# axios_sensor_rev1.net
KiCad netlist of a schematic drawn in EAGLE
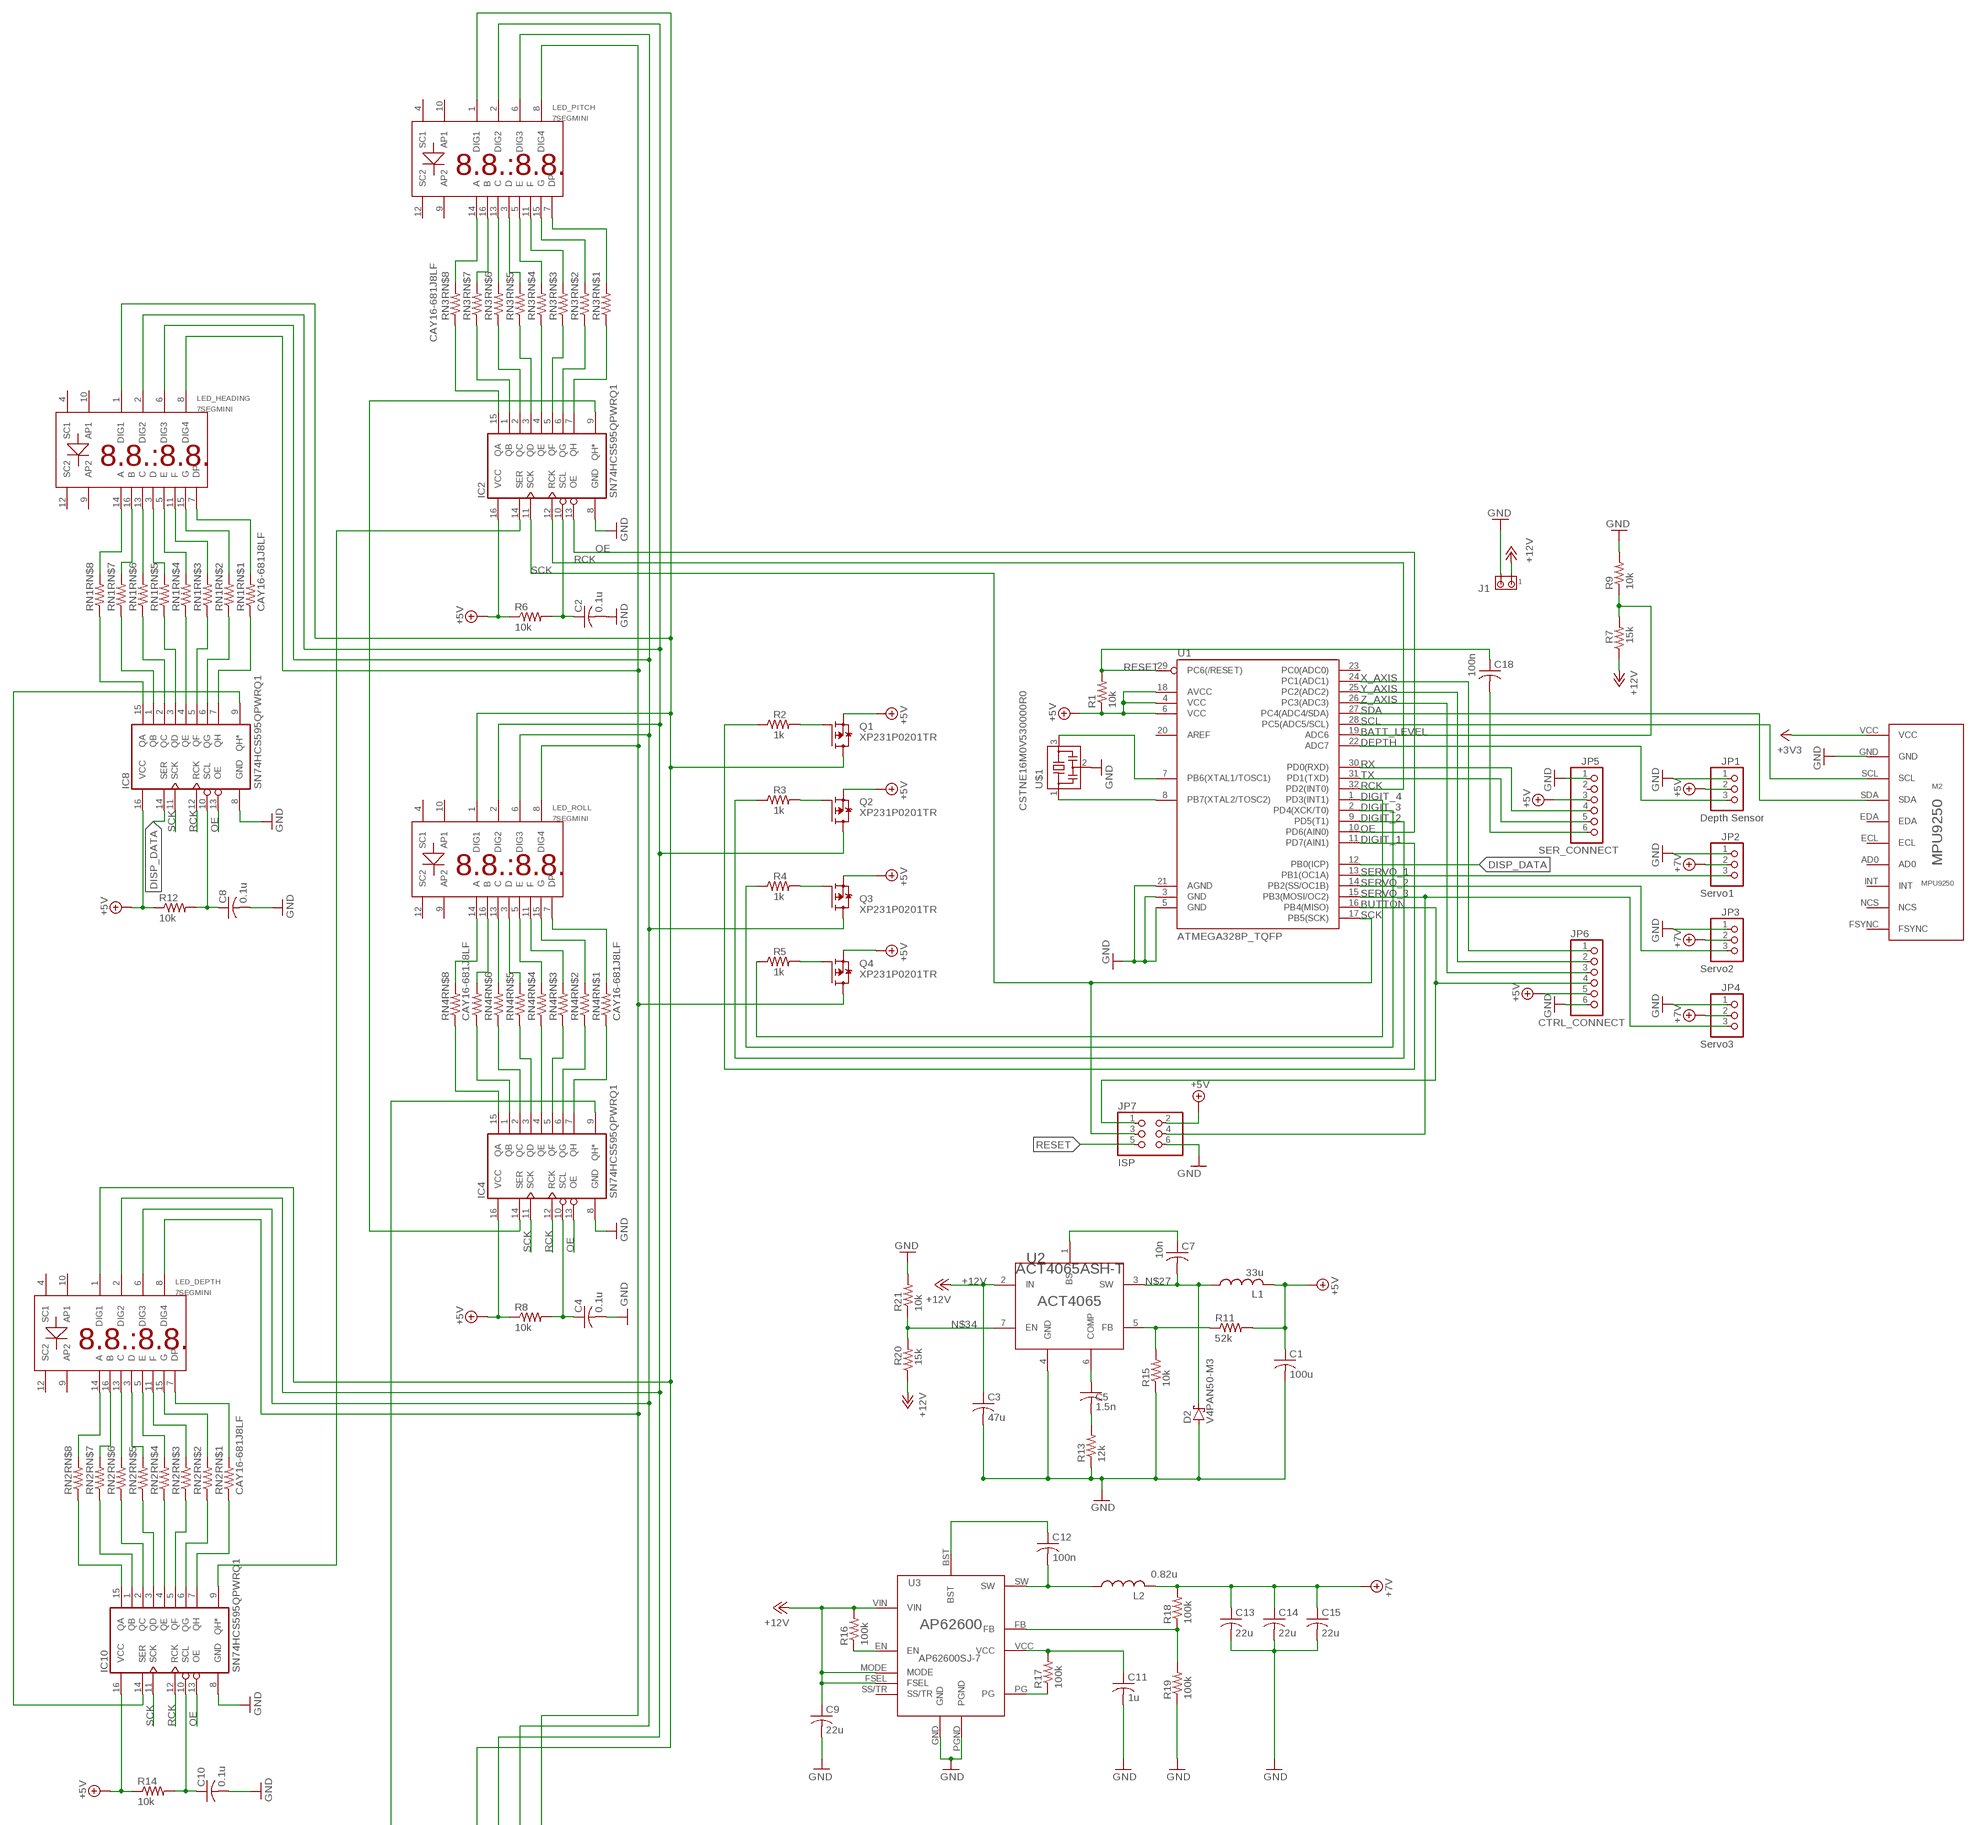
[diagram p0: schematic, sheet 1, part 1 of 2]
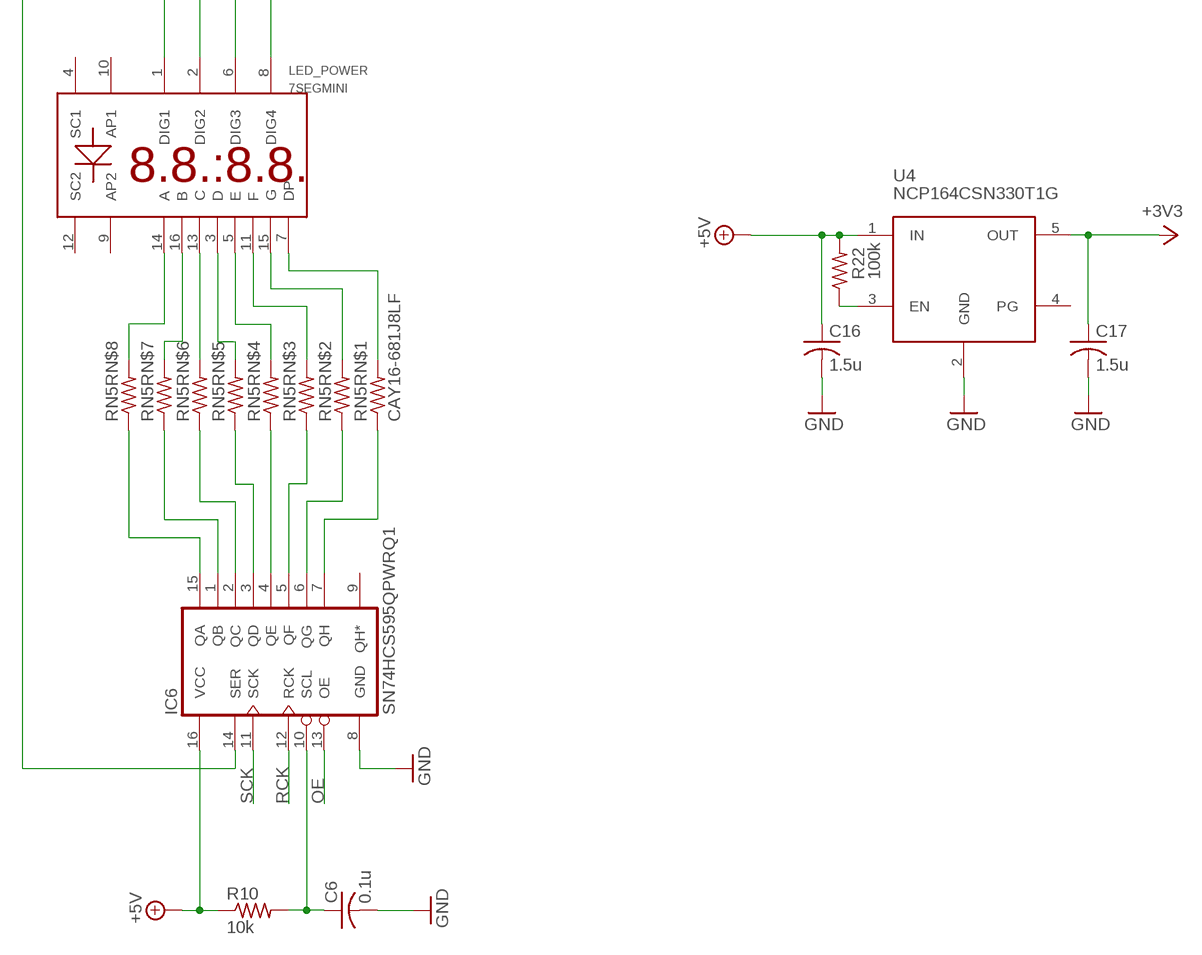
[diagram p1: schematic, sheet 1, part 2 of 2]

(export (version "E")
  (design (tool "Eeschema 10.0.6"))
  (components
    (comp (ref "C1")
      (value "100u")
      (footprint "eagle-import:C0603")
      (libsource (lib "eagle-import") (part "C-USC0603"))
    )
    (comp (ref "C2")
      (value "0.1u")
      (footprint "eagle-import:C0603")
      (libsource (lib "eagle-import") (part "C-USC0603"))
    )
    (comp (ref "C3")
      (value "47u")
      (footprint "eagle-import:C0603")
      (libsource (lib "eagle-import") (part "C-USC0603"))
    )
    (comp (ref "C4")
      (value "0.1u")
      (footprint "eagle-import:C0603")
      (libsource (lib "eagle-import") (part "C-USC0603"))
    )
    (comp (ref "C5")
      (value "1.5n")
      (footprint "eagle-import:C0603")
      (libsource (lib "eagle-import") (part "C-USC0603"))
    )
    (comp (ref "C6")
      (value "0.1u")
      (footprint "eagle-import:C0603")
      (libsource (lib "eagle-import") (part "C-USC0603"))
    )
    (comp (ref "C7")
      (value "10n")
      (footprint "eagle-import:C0603")
      (libsource (lib "eagle-import") (part "C-USC0603"))
    )
    (comp (ref "C8")
      (value "0.1u")
      (footprint "eagle-import:C0603")
      (libsource (lib "eagle-import") (part "C-USC0603"))
    )
    (comp (ref "C9")
      (value "22u")
      (footprint "eagle-import:C0603")
      (libsource (lib "eagle-import") (part "C-USC0603"))
    )
    (comp (ref "C10")
      (value "0.1u")
      (footprint "eagle-import:C0603")
      (libsource (lib "eagle-import") (part "C-USC0603"))
    )
    (comp (ref "C11")
      (value "1u")
      (footprint "eagle-import:C0603")
      (libsource (lib "eagle-import") (part "C-USC0603"))
    )
    (comp (ref "C12")
      (value "100n")
      (footprint "eagle-import:C0603")
      (libsource (lib "eagle-import") (part "C-USC0603"))
    )
    (comp (ref "C13")
      (value "22u")
      (footprint "eagle-import:C0603")
      (libsource (lib "eagle-import") (part "C-USC0603"))
    )
    (comp (ref "C14")
      (value "22u")
      (footprint "eagle-import:C0603")
      (libsource (lib "eagle-import") (part "C-USC0603"))
    )
    (comp (ref "C15")
      (value "22u")
      (footprint "eagle-import:C0603")
      (libsource (lib "eagle-import") (part "C-USC0603"))
    )
    (comp (ref "C16")
      (value "1.5u")
      (footprint "eagle-import:C0603")
      (libsource (lib "eagle-import") (part "C-USC0603"))
    )
    (comp (ref "C17")
      (value "1.5u")
      (footprint "eagle-import:C0603")
      (libsource (lib "eagle-import") (part "C-USC0603"))
    )
    (comp (ref "C18")
      (value "100n")
      (footprint "eagle-import:C0603")
      (libsource (lib "eagle-import") (part "C-USC0603"))
    )
    (comp (ref "D2")
      (value "V4PAN50-M3")
      (footprint "eagle-import:SMPA")
      (libsource (lib "eagle-import") (part "V4PAN50-M3"))
    )
    (comp (ref "IC2")
      (value "SN74HCS595QPWRQ1")
      (footprint "eagle-import:TSSOP16")
      (libsource (lib "eagle-import") (part "SN74HCS595QPWRQ1"))
    )
    (comp (ref "IC4")
      (value "SN74HCS595QPWRQ1")
      (footprint "eagle-import:TSSOP16")
      (libsource (lib "eagle-import") (part "SN74HCS595QPWRQ1"))
    )
    (comp (ref "IC6")
      (value "SN74HCS595QPWRQ1")
      (footprint "eagle-import:TSSOP16")
      (libsource (lib "eagle-import") (part "SN74HCS595QPWRQ1"))
    )
    (comp (ref "IC8")
      (value "SN74HCS595QPWRQ1")
      (footprint "eagle-import:TSSOP16")
      (libsource (lib "eagle-import") (part "SN74HCS595QPWRQ1"))
    )
    (comp (ref "IC10")
      (value "SN74HCS595QPWRQ1")
      (footprint "eagle-import:TSSOP16")
      (libsource (lib "eagle-import") (part "SN74HCS595QPWRQ1"))
    )
    (comp (ref "J1")
      (value "MTA02-156")
      (footprint "eagle-import:1X2MTA")
      (libsource (lib "eagle-import") (part "MTA02-156"))
    )
    (comp (ref "JP1")
      (value "Depth Sensor")
      (footprint "eagle-import:1X03")
      (libsource (lib "eagle-import") (part "PINHD-1X3"))
    )
    (comp (ref "JP2")
      (value "Servo1")
      (footprint "eagle-import:1X03")
      (libsource (lib "eagle-import") (part "PINHD-1X3"))
    )
    (comp (ref "JP3")
      (value "Servo2")
      (footprint "eagle-import:1X03")
      (libsource (lib "eagle-import") (part "PINHD-1X3"))
    )
    (comp (ref "JP4")
      (value "Servo3")
      (footprint "eagle-import:1X03")
      (libsource (lib "eagle-import") (part "PINHD-1X3"))
    )
    (comp (ref "JP5")
      (value "SER_CONNECT")
      (footprint "eagle-import:1X06")
      (libsource (lib "eagle-import") (part "PINHD-1X6"))
    )
    (comp (ref "JP6")
      (value "CTRL_CONNECT")
      (footprint "eagle-import:1X06")
      (libsource (lib "eagle-import") (part "PINHD-1X6"))
    )
    (comp (ref "JP7")
      (value "ISP")
      (footprint "eagle-import:2X03")
      (libsource (lib "eagle-import") (part "PINHD-2X3"))
    )
    (comp (ref "L1")
      (value "33u")
      (footprint "eagle-import:SRN1060-330M")
      (libsource (lib "eagle-import") (part "SRN1060-330M"))
    )
    (comp (ref "L2")
      (value "0.82u")
      (footprint "eagle-import:ECS-MPIL0630-R82MC")
      (libsource (lib "eagle-import") (part "ECS-MPIL0630-R82MC"))
    )
    (comp (ref "LED_DEPTH")
      (value "7SEGMINI")
      (footprint "eagle-import:7SEGMINI")
      (libsource (lib "eagle-import") (part "7SEGMINI"))
    )
    (comp (ref "LED_HEADING")
      (value "7SEGMINI")
      (footprint "eagle-import:7SEGMINI")
      (libsource (lib "eagle-import") (part "7SEGMINI"))
    )
    (comp (ref "LED_PITCH")
      (value "7SEGMINI")
      (footprint "eagle-import:7SEGMINI")
      (libsource (lib "eagle-import") (part "7SEGMINI"))
    )
    (comp (ref "LED_POWER")
      (value "7SEGMINI")
      (footprint "eagle-import:7SEGMINI")
      (libsource (lib "eagle-import") (part "7SEGMINI"))
    )
    (comp (ref "LED_ROLL")
      (value "7SEGMINI")
      (footprint "eagle-import:7SEGMINI")
      (libsource (lib "eagle-import") (part "7SEGMINI"))
    )
    (comp (ref "M2")
      (value "MPU9250")
      (footprint "eagle-import:MPU9250")
      (libsource (lib "eagle-import") (part "MPU9250"))
    )
    (comp (ref "Q1")
      (value "XP231P0201TR")
      (footprint "eagle-import:SOT23")
      (libsource (lib "eagle-import") (part "XP231P0201TR"))
    )
    (comp (ref "Q2")
      (value "XP231P0201TR")
      (footprint "eagle-import:SOT23")
      (libsource (lib "eagle-import") (part "XP231P0201TR"))
    )
    (comp (ref "Q3")
      (value "XP231P0201TR")
      (footprint "eagle-import:SOT23")
      (libsource (lib "eagle-import") (part "XP231P0201TR"))
    )
    (comp (ref "Q4")
      (value "XP231P0201TR")
      (footprint "eagle-import:SOT23")
      (libsource (lib "eagle-import") (part "XP231P0201TR"))
    )
    (comp (ref "R1")
      (value "10k")
      (footprint "eagle-import:R0603")
      (libsource (lib "eagle-import") (part "R-US_R0603"))
    )
    (comp (ref "R2")
      (value "1k")
      (footprint "eagle-import:R0603")
      (libsource (lib "eagle-import") (part "R-US_R0603"))
    )
    (comp (ref "R3")
      (value "1k")
      (footprint "eagle-import:R0603")
      (libsource (lib "eagle-import") (part "R-US_R0603"))
    )
    (comp (ref "R4")
      (value "1k")
      (footprint "eagle-import:R0603")
      (libsource (lib "eagle-import") (part "R-US_R0603"))
    )
    (comp (ref "R5")
      (value "1k")
      (footprint "eagle-import:R0603")
      (libsource (lib "eagle-import") (part "R-US_R0603"))
    )
    (comp (ref "R6")
      (value "10k")
      (footprint "eagle-import:R0603")
      (libsource (lib "eagle-import") (part "R-US_R0603"))
    )
    (comp (ref "R7")
      (value "15k")
      (footprint "eagle-import:R0603")
      (libsource (lib "eagle-import") (part "R-US_R0603"))
    )
    (comp (ref "R8")
      (value "10k")
      (footprint "eagle-import:R0603")
      (libsource (lib "eagle-import") (part "R-US_R0603"))
    )
    (comp (ref "R9")
      (value "10k")
      (footprint "eagle-import:R0603")
      (libsource (lib "eagle-import") (part "R-US_R0603"))
    )
    (comp (ref "R10")
      (value "10k")
      (footprint "eagle-import:R0603")
      (libsource (lib "eagle-import") (part "R-US_R0603"))
    )
    (comp (ref "R11")
      (value "52k")
      (footprint "eagle-import:R0603")
      (libsource (lib "eagle-import") (part "R-US_R0603"))
    )
    (comp (ref "R12")
      (value "10k")
      (footprint "eagle-import:R0603")
      (libsource (lib "eagle-import") (part "R-US_R0603"))
    )
    (comp (ref "R13")
      (value "12k")
      (footprint "eagle-import:R0603")
      (libsource (lib "eagle-import") (part "R-US_R0603"))
    )
    (comp (ref "R14")
      (value "10k")
      (footprint "eagle-import:R0603")
      (libsource (lib "eagle-import") (part "R-US_R0603"))
    )
    (comp (ref "R15")
      (value "10k")
      (footprint "eagle-import:R0603")
      (libsource (lib "eagle-import") (part "R-US_R0603"))
    )
    (comp (ref "R16")
      (value "100k")
      (footprint "eagle-import:R0603")
      (libsource (lib "eagle-import") (part "R-US_R0603"))
    )
    (comp (ref "R17")
      (value "100k")
      (footprint "eagle-import:R0603")
      (libsource (lib "eagle-import") (part "R-US_R0603"))
    )
    (comp (ref "R18")
      (value "100k")
      (footprint "eagle-import:R0603")
      (libsource (lib "eagle-import") (part "R-US_R0603"))
    )
    (comp (ref "R19")
      (value "100k")
      (footprint "eagle-import:R0603")
      (libsource (lib "eagle-import") (part "R-US_R0603"))
    )
    (comp (ref "R20")
      (value "15k")
      (footprint "eagle-import:R0603")
      (libsource (lib "eagle-import") (part "R-US_R0603"))
    )
    (comp (ref "R21")
      (value "10k")
      (footprint "eagle-import:R0603")
      (libsource (lib "eagle-import") (part "R-US_R0603"))
    )
    (comp (ref "R22")
      (value "100k")
      (footprint "eagle-import:R0603")
      (libsource (lib "eagle-import") (part "R-US_R0603"))
    )
    (comp (ref "RN1")
      (value "CAY16-681J8LF")
      (footprint "eagle-import:CAY16-681J8LF")
      (libsource (lib "eagle-import") (part "CAY16-681J8LF"))
    )
    (comp (ref "RN2")
      (value "CAY16-681J8LF")
      (footprint "eagle-import:CAY16-681J8LF")
      (libsource (lib "eagle-import") (part "CAY16-681J8LF"))
    )
    (comp (ref "RN3")
      (value "CAY16-681J8LF")
      (footprint "eagle-import:CAY16-681J8LF")
      (libsource (lib "eagle-import") (part "CAY16-681J8LF"))
    )
    (comp (ref "RN4")
      (value "CAY16-681J8LF")
      (footprint "eagle-import:CAY16-681J8LF")
      (libsource (lib "eagle-import") (part "CAY16-681J8LF"))
    )
    (comp (ref "RN5")
      (value "CAY16-681J8LF")
      (footprint "eagle-import:CAY16-681J8LF")
      (libsource (lib "eagle-import") (part "CAY16-681J8LF"))
    )
    (comp (ref "U$1")
      (value "CSTNE16M0V530000R0")
      (footprint "eagle-import:CSTCR6M")
      (libsource (lib "eagle-import") (part "CSTNE16M0V530000R0"))
    )
    (comp (ref "U1")
      (value "ATMEGA328P_TQFP")
      (footprint "eagle-import:TQFP32-08")
      (libsource (lib "eagle-import") (part "ATMEGA328P_TQFP"))
    )
    (comp (ref "U2")
      (value "ACT4065ASH-T")
      (footprint "eagle-import:SO8")
      (libsource (lib "eagle-import") (part "ACT4065ASH-T"))
    )
    (comp (ref "U3")
      (value "AP62600SJ-7")
      (footprint "eagle-import:V-QFN2030-12")
      (libsource (lib "eagle-import") (part "AP62600SJ-7"))
    )
    (comp (ref "U4")
      (value "NCP164CSN330T1G")
      (footprint "eagle-import:TSOP-5")
      (libsource (lib "eagle-import") (part "NCP164CSN330T1G"))
    )
  )
  (nets
    (net (code "1") (name "+3V3") (class "Default")
      (node (ref "C17") (pin "1") (pinfunction "1_1") (pintype "passive"))
      (node (ref "M2") (pin "VCC") (pinfunction "VCC_VCC") (pintype "bidirectional"))
      (node (ref "U4") (pin "5") (pinfunction "OUT_5") (pintype "bidirectional"))
    )
    (net (code "2") (name "+5V") (class "Default")
      (node (ref "C1") (pin "1") (pinfunction "1_1") (pintype "passive"))
      (node (ref "C16") (pin "1") (pinfunction "1_1") (pintype "passive"))
      (node (ref "IC10") (pin "16") (pinfunction "VCC_16") (pintype "power_in"))
      (node (ref "IC2") (pin "16") (pinfunction "VCC_16") (pintype "power_in"))
      (node (ref "IC4") (pin "16") (pinfunction "VCC_16") (pintype "power_in"))
      (node (ref "IC6") (pin "16") (pinfunction "VCC_16") (pintype "power_in"))
      (node (ref "IC8") (pin "16") (pinfunction "VCC_16") (pintype "power_in"))
      (node (ref "JP1") (pin "2") (pinfunction "2_2") (pintype "passive"))
      (node (ref "JP5") (pin "3") (pinfunction "3_3") (pintype "passive"))
      (node (ref "JP6") (pin "5") (pinfunction "5_5") (pintype "passive"))
      (node (ref "JP7") (pin "2") (pinfunction "2_2") (pintype "passive"))
      (node (ref "L1") (pin "P$2") (pinfunction "2_P$2") (pintype "passive"))
      (node (ref "Q1") (pin "2") (pinfunction "S_2") (pintype "passive"))
      (node (ref "Q2") (pin "2") (pinfunction "S_2") (pintype "passive"))
      (node (ref "Q3") (pin "2") (pinfunction "S_2") (pintype "passive"))
      (node (ref "Q4") (pin "2") (pinfunction "S_2") (pintype "passive"))
      (node (ref "R1") (pin "1") (pinfunction "1_1") (pintype "passive"))
      (node (ref "R10") (pin "1") (pinfunction "1_1") (pintype "passive"))
      (node (ref "R11") (pin "2") (pinfunction "2_2") (pintype "passive"))
      (node (ref "R12") (pin "1") (pinfunction "1_1") (pintype "passive"))
      (node (ref "R14") (pin "1") (pinfunction "1_1") (pintype "passive"))
      (node (ref "R22") (pin "2") (pinfunction "2_2") (pintype "passive"))
      (node (ref "R6") (pin "1") (pinfunction "1_1") (pintype "passive"))
      (node (ref "R8") (pin "1") (pinfunction "1_1") (pintype "passive"))
      (node (ref "U1") (pin "18") (pinfunction "AVCC_18") (pintype "bidirectional"))
      (node (ref "U1") (pin "4") (pinfunction "VCC_4") (pintype "bidirectional"))
      (node (ref "U1") (pin "6") (pinfunction "VCC_6") (pintype "bidirectional"))
      (node (ref "U4") (pin "1") (pinfunction "IN_1") (pintype "bidirectional"))
    )
    (net (code "3") (name "+7V") (class "Default")
      (node (ref "C13") (pin "1") (pinfunction "1_1") (pintype "passive"))
      (node (ref "C14") (pin "1") (pinfunction "1_1") (pintype "passive"))
      (node (ref "C15") (pin "1") (pinfunction "1_1") (pintype "passive"))
      (node (ref "JP2") (pin "2") (pinfunction "2_2") (pintype "passive"))
      (node (ref "JP3") (pin "2") (pinfunction "2_2") (pintype "passive"))
      (node (ref "JP4") (pin "2") (pinfunction "2_2") (pintype "passive"))
      (node (ref "L2") (pin "P$2") (pinfunction "2_P$2") (pintype "passive"))
      (node (ref "R18") (pin "2") (pinfunction "2_2") (pintype "passive"))
    )
    (net (code "4") (name "+12V") (class "Default")
      (node (ref "C3") (pin "1") (pinfunction "1_1") (pintype "passive"))
      (node (ref "C9") (pin "1") (pinfunction "1_1") (pintype "passive"))
      (node (ref "J1") (pin "1") (pinfunction "1_1") (pintype "passive"))
      (node (ref "R16") (pin "2") (pinfunction "2_2") (pintype "passive"))
      (node (ref "R20") (pin "1") (pinfunction "1_1") (pintype "passive"))
      (node (ref "R7") (pin "1") (pinfunction "1_1") (pintype "passive"))
      (node (ref "U2") (pin "2") (pinfunction "IN_2") (pintype "bidirectional"))
      (node (ref "U3") (pin "FSEL") (pinfunction "FSEL_FSEL") (pintype "bidirectional"))
      (node (ref "U3") (pin "MODE") (pinfunction "MODE_MODE") (pintype "bidirectional"))
      (node (ref "U3") (pin "VIN") (pinfunction "VIN_VIN") (pintype "bidirectional"))
    )
    (net (code "5") (name "/BATT_LEVEL") (class "Default")
      (node (ref "R7") (pin "2") (pinfunction "2_2") (pintype "passive"))
      (node (ref "R9") (pin "1") (pinfunction "1_1") (pintype "passive"))
      (node (ref "U1") (pin "19") (pinfunction "ADC6_19") (pintype "bidirectional"))
    )
    (net (code "6") (name "/BUTTON") (class "Default")
      (node (ref "JP6") (pin "4") (pinfunction "4_4") (pintype "passive"))
      (node (ref "JP7") (pin "1") (pinfunction "1_1") (pintype "passive"))
      (node (ref "U1") (pin "16") (pinfunction "PB4(MISO)_16") (pintype "bidirectional"))
    )
    (net (code "7") (name "/DEPTH") (class "Default")
      (node (ref "JP1") (pin "3") (pinfunction "3_3") (pintype "passive"))
      (node (ref "U1") (pin "22") (pinfunction "ADC7_22") (pintype "bidirectional"))
    )
    (net (code "8") (name "/DIGIT_1") (class "Default")
      (node (ref "R2") (pin "1") (pinfunction "1_1") (pintype "passive"))
      (node (ref "U1") (pin "11") (pinfunction "PD7(AIN1)_11") (pintype "bidirectional"))
    )
    (net (code "9") (name "/DIGIT_2") (class "Default")
      (node (ref "R3") (pin "1") (pinfunction "1_1") (pintype "passive"))
      (node (ref "U1") (pin "9") (pinfunction "PD5(T1)_9") (pintype "bidirectional"))
    )
    (net (code "10") (name "/DIGIT_3") (class "Default")
      (node (ref "R4") (pin "1") (pinfunction "1_1") (pintype "passive"))
      (node (ref "U1") (pin "2") (pinfunction "PD4(XCK/T0)_2") (pintype "bidirectional"))
    )
    (net (code "11") (name "/DIGIT_4") (class "Default")
      (node (ref "R5") (pin "1") (pinfunction "1_1") (pintype "passive"))
      (node (ref "U1") (pin "1") (pinfunction "PD3(INT1)_1") (pintype "bidirectional"))
    )
    (net (code "12") (name "/N$27") (class "Default")
      (node (ref "C7") (pin "2") (pinfunction "2_2") (pintype "passive"))
      (node (ref "D2") (pin "C") (pinfunction "C_C") (pintype "passive"))
      (node (ref "L1") (pin "P$1") (pinfunction "1_P$1") (pintype "passive"))
      (node (ref "U2") (pin "3") (pinfunction "SW_3") (pintype "bidirectional"))
    )
    (net (code "13") (name "/N$34") (class "Default")
      (node (ref "R20") (pin "2") (pinfunction "2_2") (pintype "passive"))
      (node (ref "R21") (pin "1") (pinfunction "1_1") (pintype "passive"))
      (node (ref "U2") (pin "7") (pinfunction "EN_7") (pintype "bidirectional"))
    )
    (net (code "14") (name "/OE") (class "Default")
      (node (ref "IC10") (pin "13") (pinfunction "OE_13") (pintype "bidirectional"))
      (node (ref "IC2") (pin "13") (pinfunction "OE_13") (pintype "bidirectional"))
      (node (ref "IC4") (pin "13") (pinfunction "OE_13") (pintype "bidirectional"))
      (node (ref "IC6") (pin "13") (pinfunction "OE_13") (pintype "bidirectional"))
      (node (ref "IC8") (pin "13") (pinfunction "OE_13") (pintype "bidirectional"))
      (node (ref "U1") (pin "10") (pinfunction "PD6(AIN0)_10") (pintype "bidirectional"))
    )
    (net (code "15") (name "/RCK") (class "Default")
      (node (ref "IC10") (pin "12") (pinfunction "RCK_12") (pintype "input"))
      (node (ref "IC2") (pin "12") (pinfunction "RCK_12") (pintype "input"))
      (node (ref "IC4") (pin "12") (pinfunction "RCK_12") (pintype "input"))
      (node (ref "IC6") (pin "12") (pinfunction "RCK_12") (pintype "input"))
      (node (ref "IC8") (pin "12") (pinfunction "RCK_12") (pintype "input"))
      (node (ref "U1") (pin "32") (pinfunction "PD2(INT0)_32") (pintype "bidirectional"))
    )
    (net (code "16") (name "/RX") (class "Default")
      (node (ref "JP5") (pin "4") (pinfunction "4_4") (pintype "passive"))
      (node (ref "U1") (pin "30") (pinfunction "PD0(RXD)_30") (pintype "bidirectional"))
    )
    (net (code "17") (name "/SCK") (class "Default")
      (node (ref "IC10") (pin "11") (pinfunction "SCK_11") (pintype "input"))
      (node (ref "IC2") (pin "11") (pinfunction "SCK_11") (pintype "input"))
      (node (ref "IC4") (pin "11") (pinfunction "SCK_11") (pintype "input"))
      (node (ref "IC6") (pin "11") (pinfunction "SCK_11") (pintype "input"))
      (node (ref "IC8") (pin "11") (pinfunction "SCK_11") (pintype "input"))
      (node (ref "JP7") (pin "3") (pinfunction "3_3") (pintype "passive"))
      (node (ref "U1") (pin "17") (pinfunction "PB5(SCK)_17") (pintype "bidirectional"))
    )
    (net (code "18") (name "/SCL") (class "Default")
      (node (ref "M2") (pin "SCL") (pinfunction "SCL_SCL") (pintype "bidirectional"))
      (node (ref "U1") (pin "28") (pinfunction "PC5(ADC5/SCL)_28") (pintype "bidirectional"))
    )
    (net (code "19") (name "/SDA") (class "Default")
      (node (ref "M2") (pin "SDA") (pinfunction "SDA_SDA") (pintype "bidirectional"))
      (node (ref "U1") (pin "27") (pinfunction "PC4(ADC4/SDA)_27") (pintype "bidirectional"))
    )
    (net (code "20") (name "/SERVO_1") (class "Default")
      (node (ref "JP2") (pin "3") (pinfunction "3_3") (pintype "passive"))
      (node (ref "U1") (pin "13") (pinfunction "PB1(OC1A)_13") (pintype "bidirectional"))
    )
    (net (code "21") (name "/SERVO_2") (class "Default")
      (node (ref "JP3") (pin "3") (pinfunction "3_3") (pintype "passive"))
      (node (ref "U1") (pin "14") (pinfunction "PB2(SS/OC1B)_14") (pintype "bidirectional"))
    )
    (net (code "22") (name "/SERVO_3") (class "Default")
      (node (ref "JP4") (pin "3") (pinfunction "3_3") (pintype "passive"))
      (node (ref "JP7") (pin "4") (pinfunction "4_4") (pintype "passive"))
      (node (ref "U1") (pin "15") (pinfunction "PB3(MOSI/OC2)_15") (pintype "bidirectional"))
    )
    (net (code "23") (name "/TX") (class "Default")
      (node (ref "JP5") (pin "5") (pinfunction "5_5") (pintype "passive"))
      (node (ref "U1") (pin "31") (pinfunction "PD1(TXD)_31") (pintype "bidirectional"))
    )
    (net (code "24") (name "/X_AXIS") (class "Default")
      (node (ref "JP6") (pin "1") (pinfunction "1_1") (pintype "passive"))
      (node (ref "U1") (pin "24") (pinfunction "PC1(ADC1)_24") (pintype "bidirectional"))
    )
    (net (code "25") (name "/Y_AXIS") (class "Default")
      (node (ref "JP6") (pin "2") (pinfunction "2_2") (pintype "passive"))
      (node (ref "U1") (pin "25") (pinfunction "PC2(ADC2)_25") (pintype "bidirectional"))
    )
    (net (code "26") (name "/Z_AXIS") (class "Default")
      (node (ref "JP6") (pin "3") (pinfunction "3_3") (pintype "passive"))
      (node (ref "U1") (pin "26") (pinfunction "PC3(ADC3)_26") (pintype "bidirectional"))
    )
    (net (code "27") (name "DISP_DATA") (class "Default")
      (node (ref "IC8") (pin "14") (pinfunction "SER_14") (pintype "input"))
      (node (ref "U1") (pin "12") (pinfunction "PB0(ICP)_12") (pintype "bidirectional"))
    )
    (net (code "28") (name "GND") (class "Default")
      (node (ref "C1") (pin "2") (pinfunction "2_2") (pintype "passive"))
      (node (ref "C10") (pin "2") (pinfunction "2_2") (pintype "passive"))
      (node (ref "C11") (pin "2") (pinfunction "2_2") (pintype "passive"))
      (node (ref "C13") (pin "2") (pinfunction "2_2") (pintype "passive"))
      (node (ref "C14") (pin "2") (pinfunction "2_2") (pintype "passive"))
      (node (ref "C15") (pin "2") (pinfunction "2_2") (pintype "passive"))
      (node (ref "C16") (pin "2") (pinfunction "2_2") (pintype "passive"))
      (node (ref "C17") (pin "2") (pinfunction "2_2") (pintype "passive"))
      (node (ref "C2") (pin "2") (pinfunction "2_2") (pintype "passive"))
      (node (ref "C3") (pin "2") (pinfunction "2_2") (pintype "passive"))
      (node (ref "C4") (pin "2") (pinfunction "2_2") (pintype "passive"))
      (node (ref "C6") (pin "2") (pinfunction "2_2") (pintype "passive"))
      (node (ref "C8") (pin "2") (pinfunction "2_2") (pintype "passive"))
      (node (ref "C9") (pin "2") (pinfunction "2_2") (pintype "passive"))
      (node (ref "D2") (pin "A") (pinfunction "A_A") (pintype "passive"))
      (node (ref "IC10") (pin "8") (pinfunction "GND_8") (pintype "power_in"))
      (node (ref "IC2") (pin "8") (pinfunction "GND_8") (pintype "power_in"))
      (node (ref "IC4") (pin "8") (pinfunction "GND_8") (pintype "power_in"))
      (node (ref "IC6") (pin "8") (pinfunction "GND_8") (pintype "power_in"))
      (node (ref "IC8") (pin "8") (pinfunction "GND_8") (pintype "power_in"))
      (node (ref "J1") (pin "2") (pinfunction "2_2") (pintype "passive"))
      (node (ref "JP1") (pin "1") (pinfunction "1_1") (pintype "passive"))
      (node (ref "JP2") (pin "1") (pinfunction "1_1") (pintype "passive"))
      (node (ref "JP3") (pin "1") (pinfunction "1_1") (pintype "passive"))
      (node (ref "JP4") (pin "1") (pinfunction "1_1") (pintype "passive"))
      (node (ref "JP5") (pin "1") (pinfunction "1_1") (pintype "passive"))
      (node (ref "JP6") (pin "6") (pinfunction "6_6") (pintype "passive"))
      (node (ref "JP7") (pin "6") (pinfunction "6_6") (pintype "passive"))
      (node (ref "M2") (pin "GND") (pinfunction "GND_GND") (pintype "bidirectional"))
      (node (ref "R13") (pin "1") (pinfunction "1_1") (pintype "passive"))
      (node (ref "R15") (pin "1") (pinfunction "1_1") (pintype "passive"))
      (node (ref "R19") (pin "1") (pinfunction "1_1") (pintype "passive"))
      (node (ref "R21") (pin "2") (pinfunction "2_2") (pintype "passive"))
      (node (ref "R9") (pin "2") (pinfunction "2_2") (pintype "passive"))
      (node (ref "U$1") (pin "2") (pinfunction "2_2") (pintype "passive"))
      (node (ref "U1") (pin "21") (pinfunction "AGND_21") (pintype "bidirectional"))
      (node (ref "U1") (pin "3") (pinfunction "GND_3") (pintype "bidirectional"))
      (node (ref "U1") (pin "5") (pinfunction "GND_5") (pintype "bidirectional"))
      (node (ref "U2") (pin "4") (pinfunction "GND_4") (pintype "bidirectional"))
      (node (ref "U3") (pin "GND") (pinfunction "GND_GND") (pintype "bidirectional"))
      (node (ref "U3") (pin "PGND") (pinfunction "PGND_PGND") (pintype "bidirectional"))
      (node (ref "U4") (pin "2") (pinfunction "GND_2") (pintype "bidirectional"))
    )
    (net (code "29") (name "Net-(C5-Pad2)") (class "Default")
      (node (ref "C5") (pin "2") (pinfunction "2_2") (pintype "passive"))
      (node (ref "R13") (pin "2") (pinfunction "2_2") (pintype "passive"))
    )
    (net (code "30") (name "Net-(C11-Pad1)") (class "Default")
      (node (ref "C11") (pin "1") (pinfunction "1_1") (pintype "passive"))
      (node (ref "R17") (pin "2") (pinfunction "2_2") (pintype "passive"))
      (node (ref "U3") (pin "VCC") (pinfunction "VCC_VCC") (pintype "bidirectional"))
    )
    (net (code "31") (name "Net-(C12-Pad1)") (class "Default")
      (node (ref "C12") (pin "1") (pinfunction "1_1") (pintype "passive"))
      (node (ref "U3") (pin "BST") (pinfunction "BST_BST") (pintype "bidirectional"))
    )
    (net (code "32") (name "Net-(C18-Pad2)") (class "Default")
      (node (ref "C18") (pin "2") (pinfunction "2_2") (pintype "passive"))
      (node (ref "JP5") (pin "6") (pinfunction "6_6") (pintype "passive"))
    )
    (net (code "33") (name "Net-(IC2-QA)") (class "Default")
      (node (ref "IC2") (pin "15") (pinfunction "QA_15") (pintype "tri_state"))
      (node (ref "RN3") (pin "8") (pinfunction "1_8") (pintype "passive"))
    )
    (net (code "34") (name "Net-(IC2-QB)") (class "Default")
      (node (ref "IC2") (pin "1") (pinfunction "QB_1") (pintype "tri_state"))
      (node (ref "RN3") (pin "7") (pinfunction "1_7") (pintype "passive"))
    )
    (net (code "35") (name "Net-(IC2-QC)") (class "Default")
      (node (ref "IC2") (pin "2") (pinfunction "QC_2") (pintype "tri_state"))
      (node (ref "RN3") (pin "6") (pinfunction "1_6") (pintype "passive"))
    )
    (net (code "36") (name "Net-(IC2-QD)") (class "Default")
      (node (ref "IC2") (pin "3") (pinfunction "QD_3") (pintype "tri_state"))
      (node (ref "RN3") (pin "5") (pinfunction "1_5") (pintype "passive"))
    )
    (net (code "37") (name "Net-(IC2-QE)") (class "Default")
      (node (ref "IC2") (pin "4") (pinfunction "QE_4") (pintype "tri_state"))
      (node (ref "RN3") (pin "4") (pinfunction "1_4") (pintype "passive"))
    )
    (net (code "38") (name "Net-(IC2-QF)") (class "Default")
      (node (ref "IC2") (pin "5") (pinfunction "QF_5") (pintype "tri_state"))
      (node (ref "RN3") (pin "3") (pinfunction "1_3") (pintype "passive"))
    )
    (net (code "39") (name "Net-(IC2-QG)") (class "Default")
      (node (ref "IC2") (pin "6") (pinfunction "QG_6") (pintype "tri_state"))
      (node (ref "RN3") (pin "2") (pinfunction "1_2") (pintype "passive"))
    )
    (net (code "40") (name "Net-(IC2-QH)") (class "Default")
      (node (ref "IC2") (pin "7") (pinfunction "QH_7") (pintype "tri_state"))
      (node (ref "RN3") (pin "1") (pinfunction "1_1") (pintype "passive"))
    )
    (net (code "41") (name "Net-(IC2-QH*)") (class "Default")
      (node (ref "IC2") (pin "9") (pinfunction "QH*_9") (pintype "tri_state"))
      (node (ref "IC4") (pin "14") (pinfunction "SER_14") (pintype "input"))
    )
    (net (code "42") (name "Net-(IC2-SCL)") (class "Default")
      (node (ref "C2") (pin "1") (pinfunction "1_1") (pintype "passive"))
      (node (ref "IC2") (pin "10") (pinfunction "SCL_10") (pintype "input"))
      (node (ref "R6") (pin "2") (pinfunction "2_2") (pintype "passive"))
    )
    (net (code "43") (name "Net-(IC4-QA)") (class "Default")
      (node (ref "IC4") (pin "15") (pinfunction "QA_15") (pintype "tri_state"))
      (node (ref "RN4") (pin "8") (pinfunction "1_8") (pintype "passive"))
    )
    (net (code "44") (name "Net-(IC4-QB)") (class "Default")
      (node (ref "IC4") (pin "1") (pinfunction "QB_1") (pintype "tri_state"))
      (node (ref "RN4") (pin "7") (pinfunction "1_7") (pintype "passive"))
    )
    (net (code "45") (name "Net-(IC4-QC)") (class "Default")
      (node (ref "IC4") (pin "2") (pinfunction "QC_2") (pintype "tri_state"))
      (node (ref "RN4") (pin "6") (pinfunction "1_6") (pintype "passive"))
    )
    (net (code "46") (name "Net-(IC4-QD)") (class "Default")
      (node (ref "IC4") (pin "3") (pinfunction "QD_3") (pintype "tri_state"))
      (node (ref "RN4") (pin "5") (pinfunction "1_5") (pintype "passive"))
    )
    (net (code "47") (name "Net-(IC4-QE)") (class "Default")
      (node (ref "IC4") (pin "4") (pinfunction "QE_4") (pintype "tri_state"))
      (node (ref "RN4") (pin "4") (pinfunction "1_4") (pintype "passive"))
    )
    (net (code "48") (name "Net-(IC4-QF)") (class "Default")
      (node (ref "IC4") (pin "5") (pinfunction "QF_5") (pintype "tri_state"))
      (node (ref "RN4") (pin "3") (pinfunction "1_3") (pintype "passive"))
    )
    (net (code "49") (name "Net-(IC4-QG)") (class "Default")
      (node (ref "IC4") (pin "6") (pinfunction "QG_6") (pintype "tri_state"))
      (node (ref "RN4") (pin "2") (pinfunction "1_2") (pintype "passive"))
    )
    (net (code "50") (name "Net-(IC4-QH)") (class "Default")
      (node (ref "IC4") (pin "7") (pinfunction "QH_7") (pintype "tri_state"))
      (node (ref "RN4") (pin "1") (pinfunction "1_1") (pintype "passive"))
    )
    (net (code "51") (name "Net-(IC4-QH*)") (class "Default")
      (node (ref "IC4") (pin "9") (pinfunction "QH*_9") (pintype "tri_state"))
      (node (ref "IC6") (pin "14") (pinfunction "SER_14") (pintype "input"))
    )
    (net (code "52") (name "Net-(IC4-SCL)") (class "Default")
      (node (ref "C4") (pin "1") (pinfunction "1_1") (pintype "passive"))
      (node (ref "IC4") (pin "10") (pinfunction "SCL_10") (pintype "input"))
      (node (ref "R8") (pin "2") (pinfunction "2_2") (pintype "passive"))
    )
    (net (code "53") (name "Net-(IC6-QA)") (class "Default")
      (node (ref "IC6") (pin "15") (pinfunction "QA_15") (pintype "tri_state"))
      (node (ref "RN5") (pin "8") (pinfunction "1_8") (pintype "passive"))
    )
    (net (code "54") (name "Net-(IC6-QB)") (class "Default")
      (node (ref "IC6") (pin "1") (pinfunction "QB_1") (pintype "tri_state"))
      (node (ref "RN5") (pin "7") (pinfunction "1_7") (pintype "passive"))
    )
    (net (code "55") (name "Net-(IC6-QC)") (class "Default")
      (node (ref "IC6") (pin "2") (pinfunction "QC_2") (pintype "tri_state"))
      (node (ref "RN5") (pin "6") (pinfunction "1_6") (pintype "passive"))
    )
    (net (code "56") (name "Net-(IC6-QD)") (class "Default")
      (node (ref "IC6") (pin "3") (pinfunction "QD_3") (pintype "tri_state"))
      (node (ref "RN5") (pin "5") (pinfunction "1_5") (pintype "passive"))
    )
    (net (code "57") (name "Net-(IC6-QE)") (class "Default")
      (node (ref "IC6") (pin "4") (pinfunction "QE_4") (pintype "tri_state"))
      (node (ref "RN5") (pin "4") (pinfunction "1_4") (pintype "passive"))
    )
    (net (code "58") (name "Net-(IC6-QF)") (class "Default")
      (node (ref "IC6") (pin "5") (pinfunction "QF_5") (pintype "tri_state"))
      (node (ref "RN5") (pin "3") (pinfunction "1_3") (pintype "passive"))
    )
    (net (code "59") (name "Net-(IC6-QG)") (class "Default")
      (node (ref "IC6") (pin "6") (pinfunction "QG_6") (pintype "tri_state"))
      (node (ref "RN5") (pin "2") (pinfunction "1_2") (pintype "passive"))
    )
    (net (code "60") (name "Net-(IC6-QH)") (class "Default")
      (node (ref "IC6") (pin "7") (pinfunction "QH_7") (pintype "tri_state"))
      (node (ref "RN5") (pin "1") (pinfunction "1_1") (pintype "passive"))
    )
    (net (code "61") (name "Net-(IC6-SCL)") (class "Default")
      (node (ref "C6") (pin "1") (pinfunction "1_1") (pintype "passive"))
      (node (ref "IC6") (pin "10") (pinfunction "SCL_10") (pintype "input"))
      (node (ref "R10") (pin "2") (pinfunction "2_2") (pintype "passive"))
    )
    (net (code "62") (name "Net-(IC8-QA)") (class "Default")
      (node (ref "IC8") (pin "15") (pinfunction "QA_15") (pintype "tri_state"))
      (node (ref "RN1") (pin "8") (pinfunction "1_8") (pintype "passive"))
    )
    (net (code "63") (name "Net-(IC8-QB)") (class "Default")
      (node (ref "IC8") (pin "1") (pinfunction "QB_1") (pintype "tri_state"))
      (node (ref "RN1") (pin "7") (pinfunction "1_7") (pintype "passive"))
    )
    (net (code "64") (name "Net-(IC8-QC)") (class "Default")
      (node (ref "IC8") (pin "2") (pinfunction "QC_2") (pintype "tri_state"))
      (node (ref "RN1") (pin "6") (pinfunction "1_6") (pintype "passive"))
    )
    (net (code "65") (name "Net-(IC8-QD)") (class "Default")
      (node (ref "IC8") (pin "3") (pinfunction "QD_3") (pintype "tri_state"))
      (node (ref "RN1") (pin "5") (pinfunction "1_5") (pintype "passive"))
    )
    (net (code "66") (name "Net-(IC8-QE)") (class "Default")
      (node (ref "IC8") (pin "4") (pinfunction "QE_4") (pintype "tri_state"))
      (node (ref "RN1") (pin "4") (pinfunction "1_4") (pintype "passive"))
    )
    (net (code "67") (name "Net-(IC8-QF)") (class "Default")
      (node (ref "IC8") (pin "5") (pinfunction "QF_5") (pintype "tri_state"))
      (node (ref "RN1") (pin "3") (pinfunction "1_3") (pintype "passive"))
    )
    (net (code "68") (name "Net-(IC8-QG)") (class "Default")
      (node (ref "IC8") (pin "6") (pinfunction "QG_6") (pintype "tri_state"))
      (node (ref "RN1") (pin "2") (pinfunction "1_2") (pintype "passive"))
    )
    (net (code "69") (name "Net-(IC8-QH)") (class "Default")
      (node (ref "IC8") (pin "7") (pinfunction "QH_7") (pintype "tri_state"))
      (node (ref "RN1") (pin "1") (pinfunction "1_1") (pintype "passive"))
    )
    (net (code "70") (name "Net-(IC8-SCL)") (class "Default")
      (node (ref "C8") (pin "1") (pinfunction "1_1") (pintype "passive"))
      (node (ref "IC8") (pin "10") (pinfunction "SCL_10") (pintype "input"))
      (node (ref "R12") (pin "2") (pinfunction "2_2") (pintype "passive"))
    )
    (net (code "71") (name "Net-(IC10-QA)") (class "Default")
      (node (ref "IC10") (pin "15") (pinfunction "QA_15") (pintype "tri_state"))
      (node (ref "RN2") (pin "8") (pinfunction "1_8") (pintype "passive"))
    )
    (net (code "72") (name "Net-(IC10-QB)") (class "Default")
      (node (ref "IC10") (pin "1") (pinfunction "QB_1") (pintype "tri_state"))
      (node (ref "RN2") (pin "7") (pinfunction "1_7") (pintype "passive"))
    )
    (net (code "73") (name "Net-(IC10-QC)") (class "Default")
      (node (ref "IC10") (pin "2") (pinfunction "QC_2") (pintype "tri_state"))
      (node (ref "RN2") (pin "6") (pinfunction "1_6") (pintype "passive"))
    )
    (net (code "74") (name "Net-(IC10-QD)") (class "Default")
      (node (ref "IC10") (pin "3") (pinfunction "QD_3") (pintype "tri_state"))
      (node (ref "RN2") (pin "5") (pinfunction "1_5") (pintype "passive"))
    )
    (net (code "75") (name "Net-(IC10-QE)") (class "Default")
      (node (ref "IC10") (pin "4") (pinfunction "QE_4") (pintype "tri_state"))
      (node (ref "RN2") (pin "4") (pinfunction "1_4") (pintype "passive"))
    )
    (net (code "76") (name "Net-(IC10-QF)") (class "Default")
      (node (ref "IC10") (pin "5") (pinfunction "QF_5") (pintype "tri_state"))
      (node (ref "RN2") (pin "3") (pinfunction "1_3") (pintype "passive"))
    )
    (net (code "77") (name "Net-(IC10-QG)") (class "Default")
      (node (ref "IC10") (pin "6") (pinfunction "QG_6") (pintype "tri_state"))
      (node (ref "RN2") (pin "2") (pinfunction "1_2") (pintype "passive"))
    )
    (net (code "78") (name "Net-(IC10-QH)") (class "Default")
      (node (ref "IC10") (pin "7") (pinfunction "QH_7") (pintype "tri_state"))
      (node (ref "RN2") (pin "1") (pinfunction "1_1") (pintype "passive"))
    )
    (net (code "79") (name "Net-(IC10-QH*)") (class "Default")
      (node (ref "IC10") (pin "9") (pinfunction "QH*_9") (pintype "tri_state"))
      (node (ref "IC2") (pin "14") (pinfunction "SER_14") (pintype "input"))
    )
    (net (code "80") (name "Net-(IC10-SCL)") (class "Default")
      (node (ref "C10") (pin "1") (pinfunction "1_1") (pintype "passive"))
      (node (ref "IC10") (pin "10") (pinfunction "SCL_10") (pintype "input"))
      (node (ref "R14") (pin "2") (pinfunction "2_2") (pintype "passive"))
    )
    (net (code "81") (name "Net-(IC10-SER)") (class "Default")
      (node (ref "IC10") (pin "14") (pinfunction "SER_14") (pintype "input"))
      (node (ref "IC8") (pin "9") (pinfunction "QH*_9") (pintype "tri_state"))
    )
    (net (code "82") (name "Net-(L2-1)") (class "Default")
      (node (ref "C12") (pin "2") (pinfunction "2_2") (pintype "passive"))
      (node (ref "L2") (pin "P$1") (pinfunction "1_P$1") (pintype "passive"))
      (node (ref "U3") (pin "SW") (pinfunction "SW_SW") (pintype "bidirectional"))
    )
    (net (code "83") (name "Net-(LED_DEPTH-A)") (class "Default")
      (node (ref "LED_DEPTH") (pin "14") (pinfunction "A_14") (pintype "bidirectional"))
      (node (ref "RN2") (pin "9") (pinfunction "2_9") (pintype "passive"))
    )
    (net (code "84") (name "Net-(LED_DEPTH-B)") (class "Default")
      (node (ref "LED_DEPTH") (pin "16") (pinfunction "B_16") (pintype "bidirectional"))
      (node (ref "RN2") (pin "10") (pinfunction "2_10") (pintype "passive"))
    )
    (net (code "85") (name "Net-(LED_DEPTH-C)") (class "Default")
      (node (ref "LED_DEPTH") (pin "13") (pinfunction "C_13") (pintype "bidirectional"))
      (node (ref "RN2") (pin "11") (pinfunction "2_11") (pintype "passive"))
    )
    (net (code "86") (name "Net-(LED_DEPTH-D)") (class "Default")
      (node (ref "LED_DEPTH") (pin "3") (pinfunction "D_3") (pintype "bidirectional"))
      (node (ref "RN2") (pin "12") (pinfunction "2_12") (pintype "passive"))
    )
    (net (code "87") (name "Net-(LED_DEPTH-DIG1)") (class "Default")
      (node (ref "LED_DEPTH") (pin "1") (pinfunction "DIG1_1") (pintype "bidirectional"))
      (node (ref "LED_HEADING") (pin "1") (pinfunction "DIG1_1") (pintype "bidirectional"))
      (node (ref "LED_PITCH") (pin "1") (pinfunction "DIG1_1") (pintype "bidirectional"))
      (node (ref "LED_POWER") (pin "1") (pinfunction "DIG1_1") (pintype "bidirectional"))
      (node (ref "LED_ROLL") (pin "1") (pinfunction "DIG1_1") (pintype "bidirectional"))
      (node (ref "Q1") (pin "3") (pinfunction "D_3") (pintype "passive"))
    )
    (net (code "88") (name "Net-(LED_DEPTH-DIG2)") (class "Default")
      (node (ref "LED_DEPTH") (pin "2") (pinfunction "DIG2_2") (pintype "bidirectional"))
      (node (ref "LED_HEADING") (pin "2") (pinfunction "DIG2_2") (pintype "bidirectional"))
      (node (ref "LED_PITCH") (pin "2") (pinfunction "DIG2_2") (pintype "bidirectional"))
      (node (ref "LED_POWER") (pin "2") (pinfunction "DIG2_2") (pintype "bidirectional"))
      (node (ref "LED_ROLL") (pin "2") (pinfunction "DIG2_2") (pintype "bidirectional"))
      (node (ref "Q2") (pin "3") (pinfunction "D_3") (pintype "passive"))
    )
    (net (code "89") (name "Net-(LED_DEPTH-DIG3)") (class "Default")
      (node (ref "LED_DEPTH") (pin "6") (pinfunction "DIG3_6") (pintype "bidirectional"))
      (node (ref "LED_HEADING") (pin "6") (pinfunction "DIG3_6") (pintype "bidirectional"))
      (node (ref "LED_PITCH") (pin "6") (pinfunction "DIG3_6") (pintype "bidirectional"))
      (node (ref "LED_POWER") (pin "6") (pinfunction "DIG3_6") (pintype "bidirectional"))
      (node (ref "LED_ROLL") (pin "6") (pinfunction "DIG3_6") (pintype "bidirectional"))
      (node (ref "Q3") (pin "3") (pinfunction "D_3") (pintype "passive"))
    )
    (net (code "90") (name "Net-(LED_DEPTH-DIG4)") (class "Default")
      (node (ref "LED_DEPTH") (pin "8") (pinfunction "DIG4_8") (pintype "bidirectional"))
      (node (ref "LED_HEADING") (pin "8") (pinfunction "DIG4_8") (pintype "bidirectional"))
      (node (ref "LED_PITCH") (pin "8") (pinfunction "DIG4_8") (pintype "bidirectional"))
      (node (ref "LED_POWER") (pin "8") (pinfunction "DIG4_8") (pintype "bidirectional"))
      (node (ref "LED_ROLL") (pin "8") (pinfunction "DIG4_8") (pintype "bidirectional"))
      (node (ref "Q4") (pin "3") (pinfunction "D_3") (pintype "passive"))
    )
    (net (code "91") (name "Net-(LED_DEPTH-DP)") (class "Default")
      (node (ref "LED_DEPTH") (pin "7") (pinfunction "DP_7") (pintype "bidirectional"))
      (node (ref "RN2") (pin "16") (pinfunction "2_16") (pintype "passive"))
    )
    (net (code "92") (name "Net-(LED_DEPTH-E)") (class "Default")
      (node (ref "LED_DEPTH") (pin "5") (pinfunction "E_5") (pintype "bidirectional"))
      (node (ref "RN2") (pin "13") (pinfunction "2_13") (pintype "passive"))
    )
    (net (code "93") (name "Net-(LED_DEPTH-F)") (class "Default")
      (node (ref "LED_DEPTH") (pin "11") (pinfunction "F_11") (pintype "bidirectional"))
      (node (ref "RN2") (pin "14") (pinfunction "2_14") (pintype "passive"))
    )
    (net (code "94") (name "Net-(LED_DEPTH-G)") (class "Default")
      (node (ref "LED_DEPTH") (pin "15") (pinfunction "G_15") (pintype "bidirectional"))
      (node (ref "RN2") (pin "15") (pinfunction "2_15") (pintype "passive"))
    )
    (net (code "95") (name "Net-(LED_HEADING-A)") (class "Default")
      (node (ref "LED_HEADING") (pin "14") (pinfunction "A_14") (pintype "bidirectional"))
      (node (ref "RN1") (pin "9") (pinfunction "2_9") (pintype "passive"))
    )
    (net (code "96") (name "Net-(LED_HEADING-B)") (class "Default")
      (node (ref "LED_HEADING") (pin "16") (pinfunction "B_16") (pintype "bidirectional"))
      (node (ref "RN1") (pin "10") (pinfunction "2_10") (pintype "passive"))
    )
    (net (code "97") (name "Net-(LED_HEADING-C)") (class "Default")
      (node (ref "LED_HEADING") (pin "13") (pinfunction "C_13") (pintype "bidirectional"))
      (node (ref "RN1") (pin "11") (pinfunction "2_11") (pintype "passive"))
    )
    (net (code "98") (name "Net-(LED_HEADING-D)") (class "Default")
      (node (ref "LED_HEADING") (pin "3") (pinfunction "D_3") (pintype "bidirectional"))
      (node (ref "RN1") (pin "12") (pinfunction "2_12") (pintype "passive"))
    )
    (net (code "99") (name "Net-(LED_HEADING-DP)") (class "Default")
      (node (ref "LED_HEADING") (pin "7") (pinfunction "DP_7") (pintype "bidirectional"))
      (node (ref "RN1") (pin "16") (pinfunction "2_16") (pintype "passive"))
    )
    (net (code "100") (name "Net-(LED_HEADING-E)") (class "Default")
      (node (ref "LED_HEADING") (pin "5") (pinfunction "E_5") (pintype "bidirectional"))
      (node (ref "RN1") (pin "13") (pinfunction "2_13") (pintype "passive"))
    )
    (net (code "101") (name "Net-(LED_HEADING-F)") (class "Default")
      (node (ref "LED_HEADING") (pin "11") (pinfunction "F_11") (pintype "bidirectional"))
      (node (ref "RN1") (pin "14") (pinfunction "2_14") (pintype "passive"))
    )
    (net (code "102") (name "Net-(LED_HEADING-G)") (class "Default")
      (node (ref "LED_HEADING") (pin "15") (pinfunction "G_15") (pintype "bidirectional"))
      (node (ref "RN1") (pin "15") (pinfunction "2_15") (pintype "passive"))
    )
    (net (code "103") (name "Net-(LED_PITCH-A)") (class "Default")
      (node (ref "LED_PITCH") (pin "14") (pinfunction "A_14") (pintype "bidirectional"))
      (node (ref "RN3") (pin "9") (pinfunction "2_9") (pintype "passive"))
    )
    (net (code "104") (name "Net-(LED_PITCH-B)") (class "Default")
      (node (ref "LED_PITCH") (pin "16") (pinfunction "B_16") (pintype "bidirectional"))
      (node (ref "RN3") (pin "10") (pinfunction "2_10") (pintype "passive"))
    )
    (net (code "105") (name "Net-(LED_PITCH-C)") (class "Default")
      (node (ref "LED_PITCH") (pin "13") (pinfunction "C_13") (pintype "bidirectional"))
      (node (ref "RN3") (pin "11") (pinfunction "2_11") (pintype "passive"))
    )
    (net (code "106") (name "Net-(LED_PITCH-D)") (class "Default")
      (node (ref "LED_PITCH") (pin "3") (pinfunction "D_3") (pintype "bidirectional"))
      (node (ref "RN3") (pin "12") (pinfunction "2_12") (pintype "passive"))
    )
    (net (code "107") (name "Net-(LED_PITCH-DP)") (class "Default")
      (node (ref "LED_PITCH") (pin "7") (pinfunction "DP_7") (pintype "bidirectional"))
      (node (ref "RN3") (pin "16") (pinfunction "2_16") (pintype "passive"))
    )
    (net (code "108") (name "Net-(LED_PITCH-E)") (class "Default")
      (node (ref "LED_PITCH") (pin "5") (pinfunction "E_5") (pintype "bidirectional"))
      (node (ref "RN3") (pin "13") (pinfunction "2_13") (pintype "passive"))
    )
    (net (code "109") (name "Net-(LED_PITCH-F)") (class "Default")
      (node (ref "LED_PITCH") (pin "11") (pinfunction "F_11") (pintype "bidirectional"))
      (node (ref "RN3") (pin "14") (pinfunction "2_14") (pintype "passive"))
    )
    (net (code "110") (name "Net-(LED_PITCH-G)") (class "Default")
      (node (ref "LED_PITCH") (pin "15") (pinfunction "G_15") (pintype "bidirectional"))
      (node (ref "RN3") (pin "15") (pinfunction "2_15") (pintype "passive"))
    )
    (net (code "111") (name "Net-(LED_POWER-A)") (class "Default")
      (node (ref "LED_POWER") (pin "14") (pinfunction "A_14") (pintype "bidirectional"))
      (node (ref "RN5") (pin "9") (pinfunction "2_9") (pintype "passive"))
    )
    (net (code "112") (name "Net-(LED_POWER-B)") (class "Default")
      (node (ref "LED_POWER") (pin "16") (pinfunction "B_16") (pintype "bidirectional"))
      (node (ref "RN5") (pin "10") (pinfunction "2_10") (pintype "passive"))
    )
    (net (code "113") (name "Net-(LED_POWER-C)") (class "Default")
      (node (ref "LED_POWER") (pin "13") (pinfunction "C_13") (pintype "bidirectional"))
      (node (ref "RN5") (pin "11") (pinfunction "2_11") (pintype "passive"))
    )
    (net (code "114") (name "Net-(LED_POWER-D)") (class "Default")
      (node (ref "LED_POWER") (pin "3") (pinfunction "D_3") (pintype "bidirectional"))
      (node (ref "RN5") (pin "12") (pinfunction "2_12") (pintype "passive"))
    )
    (net (code "115") (name "Net-(LED_POWER-DP)") (class "Default")
      (node (ref "LED_POWER") (pin "7") (pinfunction "DP_7") (pintype "bidirectional"))
      (node (ref "RN5") (pin "16") (pinfunction "2_16") (pintype "passive"))
    )
    (net (code "116") (name "Net-(LED_POWER-E)") (class "Default")
      (node (ref "LED_POWER") (pin "5") (pinfunction "E_5") (pintype "bidirectional"))
      (node (ref "RN5") (pin "13") (pinfunction "2_13") (pintype "passive"))
    )
    (net (code "117") (name "Net-(LED_POWER-F)") (class "Default")
      (node (ref "LED_POWER") (pin "11") (pinfunction "F_11") (pintype "bidirectional"))
      (node (ref "RN5") (pin "14") (pinfunction "2_14") (pintype "passive"))
    )
    (net (code "118") (name "Net-(LED_POWER-G)") (class "Default")
      (node (ref "LED_POWER") (pin "15") (pinfunction "G_15") (pintype "bidirectional"))
      (node (ref "RN5") (pin "15") (pinfunction "2_15") (pintype "passive"))
    )
    (net (code "119") (name "Net-(LED_ROLL-A)") (class "Default")
      (node (ref "LED_ROLL") (pin "14") (pinfunction "A_14") (pintype "bidirectional"))
      (node (ref "RN4") (pin "9") (pinfunction "2_9") (pintype "passive"))
    )
    (net (code "120") (name "Net-(LED_ROLL-B)") (class "Default")
      (node (ref "LED_ROLL") (pin "16") (pinfunction "B_16") (pintype "bidirectional"))
      (node (ref "RN4") (pin "10") (pinfunction "2_10") (pintype "passive"))
    )
    (net (code "121") (name "Net-(LED_ROLL-C)") (class "Default")
      (node (ref "LED_ROLL") (pin "13") (pinfunction "C_13") (pintype "bidirectional"))
      (node (ref "RN4") (pin "11") (pinfunction "2_11") (pintype "passive"))
    )
    (net (code "122") (name "Net-(LED_ROLL-D)") (class "Default")
      (node (ref "LED_ROLL") (pin "3") (pinfunction "D_3") (pintype "bidirectional"))
      (node (ref "RN4") (pin "12") (pinfunction "2_12") (pintype "passive"))
    )
    (net (code "123") (name "Net-(LED_ROLL-DP)") (class "Default")
      (node (ref "LED_ROLL") (pin "7") (pinfunction "DP_7") (pintype "bidirectional"))
      (node (ref "RN4") (pin "16") (pinfunction "2_16") (pintype "passive"))
    )
    (net (code "124") (name "Net-(LED_ROLL-E)") (class "Default")
      (node (ref "LED_ROLL") (pin "5") (pinfunction "E_5") (pintype "bidirectional"))
      (node (ref "RN4") (pin "13") (pinfunction "2_13") (pintype "passive"))
    )
    (net (code "125") (name "Net-(LED_ROLL-F)") (class "Default")
      (node (ref "LED_ROLL") (pin "11") (pinfunction "F_11") (pintype "bidirectional"))
      (node (ref "RN4") (pin "14") (pinfunction "2_14") (pintype "passive"))
    )
    (net (code "126") (name "Net-(LED_ROLL-G)") (class "Default")
      (node (ref "LED_ROLL") (pin "15") (pinfunction "G_15") (pintype "bidirectional"))
      (node (ref "RN4") (pin "15") (pinfunction "2_15") (pintype "passive"))
    )
    (net (code "127") (name "Net-(Q1-G)") (class "Default")
      (node (ref "Q1") (pin "1") (pinfunction "G_1") (pintype "passive"))
      (node (ref "R2") (pin "2") (pinfunction "2_2") (pintype "passive"))
    )
    (net (code "128") (name "Net-(Q2-G)") (class "Default")
      (node (ref "Q2") (pin "1") (pinfunction "G_1") (pintype "passive"))
      (node (ref "R3") (pin "2") (pinfunction "2_2") (pintype "passive"))
    )
    (net (code "129") (name "Net-(Q3-G)") (class "Default")
      (node (ref "Q3") (pin "1") (pinfunction "G_1") (pintype "passive"))
      (node (ref "R4") (pin "2") (pinfunction "2_2") (pintype "passive"))
    )
    (net (code "130") (name "Net-(Q4-G)") (class "Default")
      (node (ref "Q4") (pin "1") (pinfunction "G_1") (pintype "passive"))
      (node (ref "R5") (pin "2") (pinfunction "2_2") (pintype "passive"))
    )
    (net (code "131") (name "Net-(R16-Pad1)") (class "Default")
      (node (ref "R16") (pin "1") (pinfunction "1_1") (pintype "passive"))
      (node (ref "U3") (pin "EN") (pinfunction "EN_EN") (pintype "bidirectional"))
    )
    (net (code "132") (name "Net-(R17-Pad1)") (class "Default")
      (node (ref "R17") (pin "1") (pinfunction "1_1") (pintype "passive"))
      (node (ref "U3") (pin "PG") (pinfunction "PG_PG") (pintype "bidirectional"))
    )
    (net (code "133") (name "Net-(R18-Pad1)") (class "Default")
      (node (ref "R18") (pin "1") (pinfunction "1_1") (pintype "passive"))
      (node (ref "R19") (pin "2") (pinfunction "2_2") (pintype "passive"))
      (node (ref "U3") (pin "FB") (pinfunction "FB_FB") (pintype "bidirectional"))
    )
    (net (code "134") (name "Net-(U1-PB6(XTAL1{slash}TOSC1))") (class "Default")
      (node (ref "U$1") (pin "3") (pinfunction "3_3") (pintype "passive"))
      (node (ref "U1") (pin "7") (pinfunction "PB6(XTAL1/TOSC1)_7") (pintype "bidirectional"))
    )
    (net (code "135") (name "Net-(U1-PB7(XTAL2{slash}TOSC2))") (class "Default")
      (node (ref "U$1") (pin "1") (pinfunction "1_1") (pintype "passive"))
      (node (ref "U1") (pin "8") (pinfunction "PB7(XTAL2/TOSC2)_8") (pintype "bidirectional"))
    )
    (net (code "136") (name "Net-(U2-BS)") (class "Default")
      (node (ref "C7") (pin "1") (pinfunction "1_1") (pintype "passive"))
      (node (ref "U2") (pin "1") (pinfunction "BS_1") (pintype "bidirectional"))
    )
    (net (code "137") (name "Net-(U2-COMP)") (class "Default")
      (node (ref "C5") (pin "1") (pinfunction "1_1") (pintype "passive"))
      (node (ref "U2") (pin "6") (pinfunction "COMP_6") (pintype "bidirectional"))
    )
    (net (code "138") (name "Net-(U2-FB)") (class "Default")
      (node (ref "R11") (pin "1") (pinfunction "1_1") (pintype "passive"))
      (node (ref "R15") (pin "2") (pinfunction "2_2") (pintype "passive"))
      (node (ref "U2") (pin "5") (pinfunction "FB_5") (pintype "bidirectional"))
    )
    (net (code "139") (name "Net-(U4-EN)") (class "Default")
      (node (ref "R22") (pin "1") (pinfunction "1_1") (pintype "passive"))
      (node (ref "U4") (pin "3") (pinfunction "EN_3") (pintype "bidirectional"))
    )
    (net (code "140") (name "RESET") (class "Default")
      (node (ref "C18") (pin "1") (pinfunction "1_1") (pintype "passive"))
      (node (ref "JP7") (pin "5") (pinfunction "5_5") (pintype "passive"))
      (node (ref "R1") (pin "2") (pinfunction "2_2") (pintype "passive"))
      (node (ref "U1") (pin "29") (pinfunction "PC6(/RESET)_29") (pintype "bidirectional"))
    )
    (net (code "141") (name "unconnected-(IC6-QH*-Pad9)") (class "Default")
      (node (ref "IC6") (pin "9") (pinfunction "QH*_9") (pintype "tri_state"))
    )
    (net (code "142") (name "unconnected-(JP5-Pad2)") (class "Default")
      (node (ref "JP5") (pin "2") (pinfunction "2_2") (pintype "passive"))
    )
    (net (code "143") (name "unconnected-(LED_DEPTH-AP1-Pad10)") (class "Default")
      (node (ref "LED_DEPTH") (pin "10") (pinfunction "AP1_10") (pintype "bidirectional"))
    )
    (net (code "144") (name "unconnected-(LED_DEPTH-AP2-Pad9)") (class "Default")
      (node (ref "LED_DEPTH") (pin "9") (pinfunction "AP2_9") (pintype "bidirectional"))
    )
    (net (code "145") (name "unconnected-(LED_DEPTH-SC1-Pad4)") (class "Default")
      (node (ref "LED_DEPTH") (pin "4") (pinfunction "SC1_4") (pintype "bidirectional"))
    )
    (net (code "146") (name "unconnected-(LED_DEPTH-SC2-Pad12)") (class "Default")
      (node (ref "LED_DEPTH") (pin "12") (pinfunction "SC2_12") (pintype "bidirectional"))
    )
    (net (code "147") (name "unconnected-(LED_HEADING-AP1-Pad10)") (class "Default")
      (node (ref "LED_HEADING") (pin "10") (pinfunction "AP1_10") (pintype "bidirectional"))
    )
    (net (code "148") (name "unconnected-(LED_HEADING-AP2-Pad9)") (class "Default")
      (node (ref "LED_HEADING") (pin "9") (pinfunction "AP2_9") (pintype "bidirectional"))
    )
    (net (code "149") (name "unconnected-(LED_HEADING-SC1-Pad4)") (class "Default")
      (node (ref "LED_HEADING") (pin "4") (pinfunction "SC1_4") (pintype "bidirectional"))
    )
    (net (code "150") (name "unconnected-(LED_HEADING-SC2-Pad12)") (class "Default")
      (node (ref "LED_HEADING") (pin "12") (pinfunction "SC2_12") (pintype "bidirectional"))
    )
    (net (code "151") (name "unconnected-(LED_PITCH-AP1-Pad10)") (class "Default")
      (node (ref "LED_PITCH") (pin "10") (pinfunction "AP1_10") (pintype "bidirectional"))
    )
    (net (code "152") (name "unconnected-(LED_PITCH-AP2-Pad9)") (class "Default")
      (node (ref "LED_PITCH") (pin "9") (pinfunction "AP2_9") (pintype "bidirectional"))
    )
    (net (code "153") (name "unconnected-(LED_PITCH-SC1-Pad4)") (class "Default")
      (node (ref "LED_PITCH") (pin "4") (pinfunction "SC1_4") (pintype "bidirectional"))
    )
    (net (code "154") (name "unconnected-(LED_PITCH-SC2-Pad12)") (class "Default")
      (node (ref "LED_PITCH") (pin "12") (pinfunction "SC2_12") (pintype "bidirectional"))
    )
    (net (code "155") (name "unconnected-(LED_POWER-AP1-Pad10)") (class "Default")
      (node (ref "LED_POWER") (pin "10") (pinfunction "AP1_10") (pintype "bidirectional"))
    )
    (net (code "156") (name "unconnected-(LED_POWER-AP2-Pad9)") (class "Default")
      (node (ref "LED_POWER") (pin "9") (pinfunction "AP2_9") (pintype "bidirectional"))
    )
    (net (code "157") (name "unconnected-(LED_POWER-SC1-Pad4)") (class "Default")
      (node (ref "LED_POWER") (pin "4") (pinfunction "SC1_4") (pintype "bidirectional"))
    )
    (net (code "158") (name "unconnected-(LED_POWER-SC2-Pad12)") (class "Default")
      (node (ref "LED_POWER") (pin "12") (pinfunction "SC2_12") (pintype "bidirectional"))
    )
    (net (code "159") (name "unconnected-(LED_ROLL-AP1-Pad10)") (class "Default")
      (node (ref "LED_ROLL") (pin "10") (pinfunction "AP1_10") (pintype "bidirectional"))
    )
    (net (code "160") (name "unconnected-(LED_ROLL-AP2-Pad9)") (class "Default")
      (node (ref "LED_ROLL") (pin "9") (pinfunction "AP2_9") (pintype "bidirectional"))
    )
    (net (code "161") (name "unconnected-(LED_ROLL-SC1-Pad4)") (class "Default")
      (node (ref "LED_ROLL") (pin "4") (pinfunction "SC1_4") (pintype "bidirectional"))
    )
    (net (code "162") (name "unconnected-(LED_ROLL-SC2-Pad12)") (class "Default")
      (node (ref "LED_ROLL") (pin "12") (pinfunction "SC2_12") (pintype "bidirectional"))
    )
    (net (code "163") (name "unconnected-(M2-PadAD0)") (class "Default")
      (node (ref "M2") (pin "AD0") (pinfunction "AD0_AD0") (pintype "bidirectional"))
    )
    (net (code "164") (name "unconnected-(M2-PadECL)") (class "Default")
      (node (ref "M2") (pin "ECL") (pinfunction "ECL_ECL") (pintype "bidirectional"))
    )
    (net (code "165") (name "unconnected-(M2-PadEDA)") (class "Default")
      (node (ref "M2") (pin "EDA") (pinfunction "EDA_EDA") (pintype "bidirectional"))
    )
    (net (code "166") (name "unconnected-(M2-PadFSYNC)") (class "Default")
      (node (ref "M2") (pin "FSYNC") (pinfunction "FSYNC_FSYNC") (pintype "bidirectional"))
    )
    (net (code "167") (name "unconnected-(M2-PadINT)") (class "Default")
      (node (ref "M2") (pin "INT") (pinfunction "INT_INT") (pintype "bidirectional"))
    )
    (net (code "168") (name "unconnected-(M2-PadNCS)") (class "Default")
      (node (ref "M2") (pin "NCS") (pinfunction "NCS_NCS") (pintype "bidirectional"))
    )
    (net (code "169") (name "unconnected-(U1-AREF-Pad20)") (class "Default")
      (node (ref "U1") (pin "20") (pinfunction "AREF_20") (pintype "bidirectional"))
    )
    (net (code "170") (name "unconnected-(U1-PC0(ADC0)-Pad23)") (class "Default")
      (node (ref "U1") (pin "23") (pinfunction "PC0(ADC0)_23") (pintype "bidirectional"))
    )
    (net (code "171") (name "unconnected-(U3-PadSS{slash}TR)") (class "Default")
      (node (ref "U3") (pin "SS/TR") (pinfunction "SS/TR_SS/TR") (pintype "bidirectional"))
    )
    (net (code "172") (name "unconnected-(U4-PG-Pad4)") (class "Default")
      (node (ref "U4") (pin "4") (pinfunction "PG_4") (pintype "bidirectional"))
    )
  )
)
